# GPS.net
KiCad netlist of a schematic drawn in Altium Designer
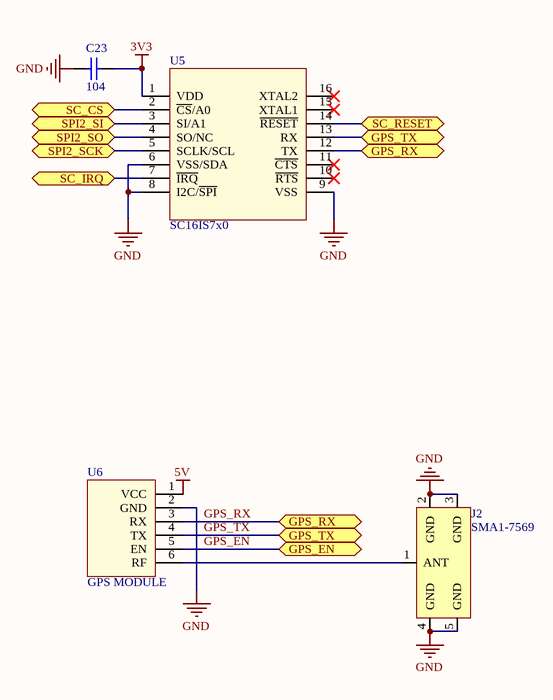
[diagram p0: GPS.SchDoc]

(export (version "E")
  (design (tool "Eeschema 10.0.6"))
  (components
    (comp (ref "C23")
      (value "104")
      (footprint "C0603")
      (description "CAP CER 0.1UF 16V Y5V 0402")
      (fields
        (field (name "MANUFACTURER") "Yageo")
        (field (name "DIGI-KEY PART NUMBER") "311-1047-1-ND")
        (field (name "PUBLISHER") "Altium Limited")
      )
      (libsource (lib "RobotClub") (part "Cap_SMT"))
    )
    (comp (ref "J2")
      (value "SMA1-7569")
      (footprint "ANTENA STAND")
      (description "SMA-R/A-F")
      (fields (field (name "DIGI-KEY PART NUMBER") "NA"))
      (libsource (lib "RobotClub") (part "SMA-R/A-F"))
    )
    (comp (ref "U5")
      (value "SC16IS7x0")
      (footprint "SSOP16_M")
      (libsource (lib "RobotClub") (part "SC16IS7x0"))
    )
    (comp (ref "U6")
      (value "GPS MODULE")
      (footprint "GPS DEMETER")
      (libsource (lib "RobotClub") (part "GPS MODULE"))
    )
  )
  (nets
    (net (code "1") (name "/GPS_EN") (class "Default")
      (node (ref "U6") (pin "5") (pinfunction "EN_5") (pintype "passive"))
    )
    (net (code "2") (name "/GPS_RX") (class "Default")
      (node (ref "U5") (pin "12") (pinfunction "TX_12") (pintype "passive"))
      (node (ref "U6") (pin "3") (pinfunction "RX_3") (pintype "passive"))
    )
    (net (code "3") (name "/GPS_TX") (class "Default")
      (node (ref "U5") (pin "13") (pinfunction "RX_13") (pintype "passive"))
      (node (ref "U6") (pin "4") (pinfunction "TX_4") (pintype "passive"))
    )
    (net (code "4") (name "/SC_CS") (class "Default")
      (node (ref "U5") (pin "2") (pinfunction "~{CS}/A0_2") (pintype "passive"))
    )
    (net (code "5") (name "/SC_IRQ") (class "Default")
      (node (ref "U5") (pin "7") (pinfunction "~{IRQ}_7") (pintype "passive"))
    )
    (net (code "6") (name "/SC_RESET") (class "Default")
      (node (ref "U5") (pin "14") (pinfunction "~{RESET}_14") (pintype "passive"))
    )
    (net (code "7") (name "/SPI2_SCK") (class "Default")
      (node (ref "U5") (pin "5") (pinfunction "SCLK/SCL_5") (pintype "passive"))
    )
    (net (code "8") (name "/SPI2_SI") (class "Default")
      (node (ref "U5") (pin "3") (pinfunction "SI/A1_3") (pintype "passive"))
    )
    (net (code "9") (name "/SPI2_SO") (class "Default")
      (node (ref "U5") (pin "4") (pinfunction "SO/NC_4") (pintype "passive"))
    )
    (net (code "10") (name "3V3") (class "Default")
      (node (ref "C23") (pin "2") (pinfunction "2_2") (pintype "passive"))
      (node (ref "U5") (pin "1") (pinfunction "VDD_1") (pintype "passive"))
    )
    (net (code "11") (name "5V") (class "Default")
      (node (ref "U6") (pin "1") (pinfunction "VCC_1") (pintype "passive"))
    )
    (net (code "12") (name "GND") (class "Default")
      (node (ref "C23") (pin "1") (pinfunction "1_1") (pintype "passive"))
      (node (ref "J2") (pin "2") (pinfunction "GND_2") (pintype "passive"))
      (node (ref "J2") (pin "3") (pinfunction "GND_3") (pintype "passive"))
      (node (ref "J2") (pin "4") (pinfunction "GND_4") (pintype "passive"))
      (node (ref "J2") (pin "5") (pinfunction "GND_5") (pintype "passive"))
      (node (ref "U5") (pin "6") (pinfunction "VSS/SDA_6") (pintype "passive"))
      (node (ref "U5") (pin "8") (pinfunction "I2C/~{SPI}_8") (pintype "passive"))
      (node (ref "U5") (pin "9") (pinfunction "VSS_9") (pintype "passive"))
      (node (ref "U6") (pin "2") (pinfunction "GND_2") (pintype "passive"))
    )
    (net (code "13") (name "Net-(J2-ANT)") (class "Default")
      (node (ref "J2") (pin "1") (pinfunction "ANT_1") (pintype "passive"))
      (node (ref "U6") (pin "6") (pinfunction "RF_6") (pintype "passive"))
    )
    (net (code "14") (name "unconnected-(U5-XTAL1-Pad15)") (class "Default")
      (node (ref "U5") (pin "15") (pinfunction "XTAL1_15") (pintype "passive+no_connect"))
    )
    (net (code "15") (name "unconnected-(U5-XTAL2-Pad16)") (class "Default")
      (node (ref "U5") (pin "16") (pinfunction "XTAL2_16") (pintype "passive+no_connect"))
    )
    (net (code "16") (name "unconnected-(U5-~{CTS}-Pad11)") (class "Default")
      (node (ref "U5") (pin "11") (pinfunction "~{CTS}_11") (pintype "passive+no_connect"))
    )
    (net (code "17") (name "unconnected-(U5-~{RTS}-Pad10)") (class "Default")
      (node (ref "U5") (pin "10") (pinfunction "~{RTS}_10") (pintype "passive+no_connect"))
    )
  )
)
